# GPS_LORA_IMU.net
KiCad netlist of a schematic drawn in Altium Designer
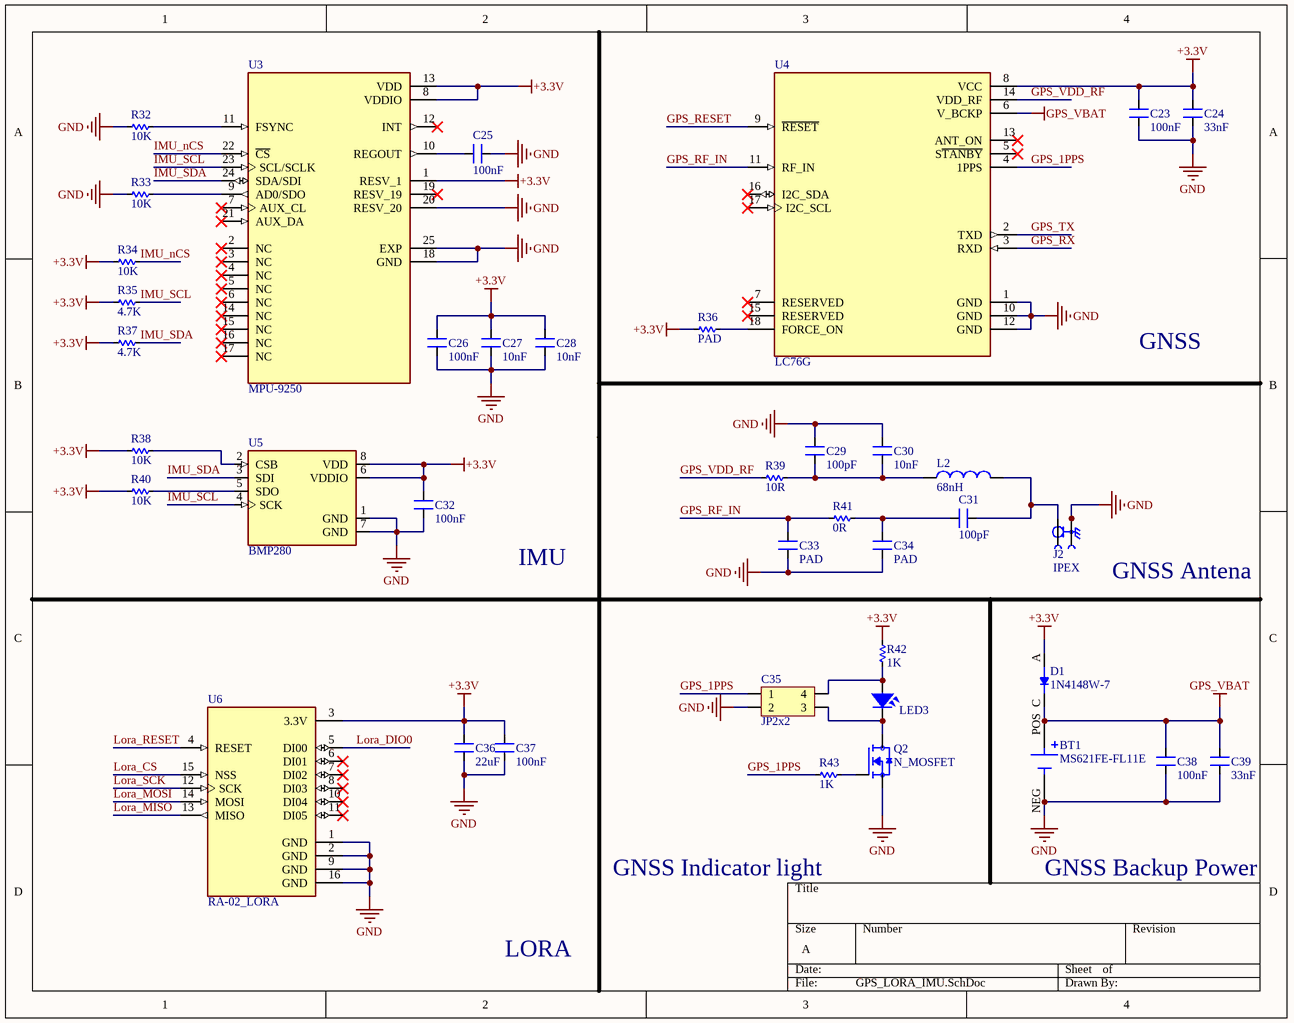
[diagram p0: GPS_LORA_IMU.SchDoc]

(export (version "E")
  (design (tool "Eeschema 10.0.6"))
  (components
    (comp (ref "BT1")
      (value "MS621FE-FL11E")
      (footprint "BAT_MS621FE-FL11E")
      (description "Coin, 6.8mm 3 V Lithium Battery Rechargeable (Secondary) 5.5mAh")
      (fields (field (name "MF") "Seiko Instruments"))
      (libsource (lib "DATN_LIB") (part "MS621FE-FL11E"))
    )
    (comp (ref "C23") (value "100nF") (footprint "CN-SMD-0603") (libsource (lib "DATN_LIB") (part "Cap-SMD")))
    (comp (ref "C24") (value "33nF") (footprint "CN-SMD-0603") (libsource (lib "DATN_LIB") (part "Cap-SMD")))
    (comp (ref "C25") (value "100nF") (footprint "CN-SMD-0603") (libsource (lib "DATN_LIB") (part "Cap-SMD")))
    (comp (ref "C26") (value "100nF") (footprint "CN-SMD-0603") (libsource (lib "DATN_LIB") (part "Cap-SMD")))
    (comp (ref "C27") (value "10nF") (footprint "CN-SMD-0603") (libsource (lib "DATN_LIB") (part "Cap-SMD")))
    (comp (ref "C28") (value "10nF") (footprint "CN-SMD-0603") (libsource (lib "DATN_LIB") (part "Cap-SMD")))
    (comp (ref "C29") (value "100pF") (footprint "CN-SMD-0603") (libsource (lib "DATN_LIB") (part "Cap-SMD")))
    (comp (ref "C30") (value "10nF") (footprint "CN-SMD-0603") (libsource (lib "DATN_LIB") (part "Cap-SMD")))
    (comp (ref "C31") (value "100pF") (footprint "CN-SMD-0603") (libsource (lib "DATN_LIB") (part "Cap-SMD")))
    (comp (ref "C32") (value "100nF") (footprint "CN-SMD-0603") (libsource (lib "DATN_LIB") (part "Cap-SMD")))
    (comp (ref "C33")
      (value "PAD")
      (footprint "PAD-CAP-SMD-0603")
      (libsource (lib "DATN_LIB") (part "Cap-SMD"))
    )
    (comp (ref "C34")
      (value "PAD")
      (footprint "PAD-CAP-SMD-0603")
      (libsource (lib "DATN_LIB") (part "Cap-SMD"))
    )
    (comp (ref "C35")
      (value "JP2x2")
      (footprint "JP2-D2T")
      (description "WR-PHD 2.54 mm Dual Socket Header")
      (fields
        (field (name "MANUFACTURER") "Würth Elektronik eiSos GmbH")
        (field (name "PARTNO") "61300421821")
        (field (name "CREATED BY") "Karrer Zheng")
      )
      (libsource (lib "DATN_LIB") (part "JP2x2"))
    )
    (comp (ref "C36") (value "22uF") (footprint "CN-SMD-1206") (libsource (lib "DATN_LIB") (part "Cap-SMD")))
    (comp (ref "C37") (value "100nF") (footprint "CN-SMD-0603") (libsource (lib "DATN_LIB") (part "Cap-SMD")))
    (comp (ref "C38") (value "100nF") (footprint "CN-SMD-0603") (libsource (lib "DATN_LIB") (part "Cap-SMD")))
    (comp (ref "C39") (value "33nF") (footprint "CN-SMD-0603") (libsource (lib "DATN_LIB") (part "Cap-SMD")))
    (comp (ref "D1")
      (value "1N4148W-7")
      (footprint "SOD3715X135N")
      (description "Diode Standard 100 V 300mA (DC) Surface Mount SOD-123")
      (fields (field (name "MF") "Diodes Inc."))
      (libsource (lib "DATN_LIB") (part "1N4148W-7"))
    )
    (comp (ref "J2")
      (value "IPEX")
      (footprint "IPEX_20279-001E-03")
      (fields (field (name "MF") "I-PEX") (field (name "MP") "20279-001E-03"))
      (libsource (lib "DATN_LIB") (part "IPEX"))
    )
    (comp (ref "L2")
      (value "68nH")
      (footprint "SMD_Inductor_0603")
      (description "INDUCTOR wire-wound")
      (fields (field (name "MP") "LQW2BAN68NG00L"))
      (libsource (lib "DATN_LIB") (part "SMD-Wire-Inductor"))
    )
    (comp (ref "LED3")
      (value "LED")
      (footprint "LED-0805-Green")
      (libsource (lib "DATN_LIB") (part "LED SMD"))
    )
    (comp (ref "Q2")
      (value "N_MOSFET")
      (footprint "SOT-23-3")
      (fields (field (name "MF") "Vishay Siliconix") (field (name "MP") "SI2306BDS-T1-GE3"))
      (libsource (lib "DATN_LIB") (part "N_MOSFET"))
    )
    (comp (ref "R32")
      (value "10K")
      (footprint "RES-SMD-0603")
      (fields
        (field (name "MANUFACTURER") "Generic Components")
        (field (name "PUBLISHER") "Altium Hobart Technology Centre")
      )
      (libsource (lib "DATN_LIB") (part "Res-SMD"))
    )
    (comp (ref "R33")
      (value "10K")
      (footprint "RES-SMD-0603")
      (fields
        (field (name "MANUFACTURER") "Generic Components")
        (field (name "PUBLISHER") "Altium Hobart Technology Centre")
      )
      (libsource (lib "DATN_LIB") (part "Res-SMD"))
    )
    (comp (ref "R34")
      (value "10K")
      (footprint "RES-SMD-0603")
      (fields
        (field (name "MANUFACTURER") "Generic Components")
        (field (name "PUBLISHER") "Altium Hobart Technology Centre")
      )
      (libsource (lib "DATN_LIB") (part "Res-SMD"))
    )
    (comp (ref "R35")
      (value "4.7K")
      (footprint "RES-SMD-0603")
      (fields
        (field (name "MANUFACTURER") "Generic Components")
        (field (name "PUBLISHER") "Altium Hobart Technology Centre")
      )
      (libsource (lib "DATN_LIB") (part "Res-SMD"))
    )
    (comp (ref "R36")
      (value "PAD")
      (footprint "PAD-RES-SMD-0603")
      (description "Resistor")
      (fields
        (field (name "MANUFACTURER") "Generic Components")
        (field (name "PUBLISHER") "Altium Hobart Technology Centre")
      )
      (libsource (lib "DATN_LIB") (part "Res-SMD"))
    )
    (comp (ref "R37")
      (value "4.7K")
      (footprint "RES-SMD-0603")
      (fields
        (field (name "MANUFACTURER") "Generic Components")
        (field (name "PUBLISHER") "Altium Hobart Technology Centre")
      )
      (libsource (lib "DATN_LIB") (part "Res-SMD"))
    )
    (comp (ref "R38")
      (value "10K")
      (footprint "RES-SMD-0603")
      (fields
        (field (name "MANUFACTURER") "Generic Components")
        (field (name "PUBLISHER") "Altium Hobart Technology Centre")
      )
      (libsource (lib "DATN_LIB") (part "Res-SMD"))
    )
    (comp (ref "R39")
      (value "10R")
      (footprint "RES-SMD-0603")
      (description "Resistor")
      (fields
        (field (name "MANUFACTURER") "Generic Components")
        (field (name "PUBLISHER") "Altium Hobart Technology Centre")
      )
      (libsource (lib "DATN_LIB") (part "Res-SMD"))
    )
    (comp (ref "R40")
      (value "10K")
      (footprint "RES-SMD-0603")
      (fields
        (field (name "MANUFACTURER") "Generic Components")
        (field (name "PUBLISHER") "Altium Hobart Technology Centre")
      )
      (libsource (lib "DATN_LIB") (part "Res-SMD"))
    )
    (comp (ref "R41")
      (value "0R")
      (footprint "RES-SMD-0603")
      (description "Resistor")
      (fields
        (field (name "MANUFACTURER") "Generic Components")
        (field (name "PUBLISHER") "Altium Hobart Technology Centre")
      )
      (libsource (lib "DATN_LIB") (part "Res-SMD"))
    )
    (comp (ref "R42")
      (value "1K")
      (footprint "RES-SMD-0603")
      (description "Resistor")
      (fields
        (field (name "MANUFACTURER") "Generic Components")
        (field (name "PUBLISHER") "Altium Hobart Technology Centre")
      )
      (libsource (lib "DATN_LIB") (part "Res-SMD"))
    )
    (comp (ref "R43")
      (value "1K")
      (footprint "RES-SMD-0603")
      (description "Resistor")
      (fields
        (field (name "MANUFACTURER") "Generic Components")
        (field (name "PUBLISHER") "Altium Hobart Technology Centre")
      )
      (libsource (lib "DATN_LIB") (part "Res-SMD"))
    )
    (comp (ref "U3")
      (value "MPU-9250")
      (footprint "QFN40P300X300X105-25N")
      (fields (field (name "MF") "TDK InvenSense"))
      (libsource (lib "DATN_LIB") (part "MPU-9250"))
    )
    (comp (ref "U4")
      (value "LC76G")
      (footprint "XCVR_LC76G")
      (fields (field (name "MF") "Quectel"))
      (libsource (lib "DATN_LIB") (part "LC76G"))
    )
    (comp (ref "U5")
      (value "BMP280")
      (footprint "XDCR_BMP280")
      (description "BMP280 Absolute Barometric Pressure Sensor for Battery Powered Devices 2 x 2.5mm")
      (libsource (lib "DATN_LIB") (part "BMP280"))
    )
    (comp (ref "U6")
      (value "RA-02_LORA")
      (footprint "MODULE_RA-02_LORA")
      (description "Ra-02 LoRa RF M5Stack Platform Evaluation Expansion Board")
      (libsource (lib "DATN_LIB") (part "RA-02_LORA"))
    )
  )
  (nets
    (net (code "1") (name "+3.3V") (class "Default")
      (node (ref "C23") (pin "2") (pinfunction "2_2") (pintype "passive"))
      (node (ref "C24") (pin "2") (pinfunction "2_2") (pintype "passive"))
      (node (ref "C26") (pin "2") (pinfunction "2_2") (pintype "passive"))
      (node (ref "C27") (pin "2") (pinfunction "2_2") (pintype "passive"))
      (node (ref "C28") (pin "2") (pinfunction "2_2") (pintype "passive"))
      (node (ref "C32") (pin "2") (pinfunction "2_2") (pintype "passive"))
      (node (ref "C36") (pin "2") (pinfunction "2_2") (pintype "passive"))
      (node (ref "C37") (pin "2") (pinfunction "2_2") (pintype "passive"))
      (node (ref "D1") (pin "A") (pinfunction "A_A") (pintype "passive"))
      (node (ref "R34") (pin "1") (pinfunction "1_1") (pintype "passive"))
      (node (ref "R35") (pin "1") (pinfunction "1_1") (pintype "passive"))
      (node (ref "R36") (pin "2") (pinfunction "2_2") (pintype "passive"))
      (node (ref "R37") (pin "1") (pinfunction "1_1") (pintype "passive"))
      (node (ref "R38") (pin "2") (pinfunction "2_2") (pintype "passive"))
      (node (ref "R40") (pin "2") (pinfunction "2_2") (pintype "passive"))
      (node (ref "R42") (pin "2") (pinfunction "2_2") (pintype "passive"))
      (node (ref "U3") (pin "1") (pinfunction "RESV_1_1") (pintype "power_in"))
      (node (ref "U3") (pin "13") (pinfunction "VDD_13") (pintype "power_in"))
      (node (ref "U3") (pin "8") (pinfunction "VDDIO_8") (pintype "power_in"))
      (node (ref "U4") (pin "8") (pinfunction "VCC_8") (pintype "power_in"))
      (node (ref "U5") (pin "6") (pinfunction "VDDIO_6") (pintype "power_in"))
      (node (ref "U5") (pin "8") (pinfunction "VDD_8") (pintype "power_in"))
      (node (ref "U6") (pin "3") (pinfunction "3.3V_3") (pintype "power_in"))
    )
    (net (code "2") (name "/GPS_1PPS") (class "Default")
      (node (ref "C35") (pin "1") (pinfunction "1_1") (pintype "passive"))
      (node (ref "R43") (pin "1") (pinfunction "1_1") (pintype "passive"))
      (node (ref "U4") (pin "4") (pinfunction "1PPS_4") (pintype "passive"))
    )
    (net (code "3") (name "/GPS_RESET") (class "Default")
      (node (ref "U4") (pin "9") (pinfunction "~{RESET}_9") (pintype "input"))
    )
    (net (code "4") (name "/GPS_RF_IN") (class "Default")
      (node (ref "C33") (pin "1") (pinfunction "1_1") (pintype "passive"))
      (node (ref "R41") (pin "2") (pinfunction "2_2") (pintype "passive"))
      (node (ref "U4") (pin "11") (pinfunction "RF_IN_11") (pintype "input"))
    )
    (net (code "5") (name "/GPS_RX") (class "Default")
      (node (ref "U4") (pin "3") (pinfunction "RXD_3") (pintype "input"))
    )
    (net (code "6") (name "/GPS_TX") (class "Default")
      (node (ref "U4") (pin "2") (pinfunction "TXD_2") (pintype "output"))
    )
    (net (code "7") (name "/GPS_VDD_RF") (class "Default")
      (node (ref "R39") (pin "2") (pinfunction "2_2") (pintype "passive"))
      (node (ref "U4") (pin "14") (pinfunction "VDD_RF_14") (pintype "power_in"))
    )
    (net (code "8") (name "/IMU_SCL") (class "Default")
      (node (ref "R35") (pin "2") (pinfunction "2_2") (pintype "passive"))
      (node (ref "U3") (pin "23") (pinfunction "SCL/SCLK_23") (pintype "input"))
      (node (ref "U5") (pin "4") (pinfunction "SCK_4") (pintype "input"))
    )
    (net (code "9") (name "/IMU_SDA") (class "Default")
      (node (ref "R37") (pin "2") (pinfunction "2_2") (pintype "passive"))
      (node (ref "U3") (pin "24") (pinfunction "SDA/SDI_24") (pintype "bidirectional"))
      (node (ref "U5") (pin "3") (pinfunction "SDI_3") (pintype "bidirectional"))
    )
    (net (code "10") (name "/IMU_nCS") (class "Default")
      (node (ref "R34") (pin "2") (pinfunction "2_2") (pintype "passive"))
      (node (ref "U3") (pin "22") (pinfunction "~{CS}_22") (pintype "input"))
    )
    (net (code "11") (name "/Lora_CS") (class "Default")
      (node (ref "U6") (pin "15") (pinfunction "NSS_15") (pintype "input"))
    )
    (net (code "12") (name "/Lora_DIO0") (class "Default")
      (node (ref "U6") (pin "5") (pinfunction "DI00_5") (pintype "bidirectional"))
    )
    (net (code "13") (name "/Lora_MISO") (class "Default")
      (node (ref "U6") (pin "13") (pinfunction "MISO_13") (pintype "output"))
    )
    (net (code "14") (name "/Lora_MOSI") (class "Default")
      (node (ref "U6") (pin "14") (pinfunction "MOSI_14") (pintype "input"))
    )
    (net (code "15") (name "/Lora_RESET") (class "Default")
      (node (ref "U6") (pin "4") (pinfunction "RESET_4") (pintype "input"))
    )
    (net (code "16") (name "/Lora_SCK") (class "Default")
      (node (ref "U6") (pin "12") (pinfunction "SCK_12") (pintype "input"))
    )
    (net (code "17") (name "GND") (class "Default")
      (node (ref "BT1") (pin "NEG") (pinfunction "NEG_NEG") (pintype "passive"))
      (node (ref "C23") (pin "1") (pinfunction "1_1") (pintype "passive"))
      (node (ref "C24") (pin "1") (pinfunction "1_1") (pintype "passive"))
      (node (ref "C25") (pin "2") (pinfunction "2_2") (pintype "passive"))
      (node (ref "C26") (pin "1") (pinfunction "1_1") (pintype "passive"))
      (node (ref "C27") (pin "1") (pinfunction "1_1") (pintype "passive"))
      (node (ref "C28") (pin "1") (pinfunction "1_1") (pintype "passive"))
      (node (ref "C29") (pin "2") (pinfunction "2_2") (pintype "passive"))
      (node (ref "C30") (pin "2") (pinfunction "2_2") (pintype "passive"))
      (node (ref "C32") (pin "1") (pinfunction "1_1") (pintype "passive"))
      (node (ref "C33") (pin "2") (pinfunction "2_2") (pintype "passive"))
      (node (ref "C34") (pin "2") (pinfunction "2_2") (pintype "passive"))
      (node (ref "C35") (pin "2") (pinfunction "2_2") (pintype "passive"))
      (node (ref "C36") (pin "1") (pinfunction "1_1") (pintype "passive"))
      (node (ref "C37") (pin "1") (pinfunction "1_1") (pintype "passive"))
      (node (ref "C38") (pin "1") (pinfunction "1_1") (pintype "passive"))
      (node (ref "C39") (pin "1") (pinfunction "1_1") (pintype "passive"))
      (node (ref "J2") (pin "2") (pinfunction "GROUND_2") (pintype "passive"))
      (node (ref "J2") (pin "3") (pinfunction "GROUND_3") (pintype "passive"))
      (node (ref "Q2") (pin "2") (pinfunction "S_2") (pintype "passive"))
      (node (ref "R32") (pin "2") (pinfunction "2_2") (pintype "passive"))
      (node (ref "R33") (pin "2") (pinfunction "2_2") (pintype "passive"))
      (node (ref "U3") (pin "18") (pinfunction "GND_18") (pintype "power_in"))
      (node (ref "U3") (pin "20") (pinfunction "RESV_20_20") (pintype "power_in"))
      (node (ref "U3") (pin "25") (pinfunction "EXP_25") (pintype "passive"))
      (node (ref "U4") (pin "1") (pinfunction "GND_1") (pintype "power_in"))
      (node (ref "U4") (pin "10") (pinfunction "GND_10") (pintype "power_in"))
      (node (ref "U4") (pin "12") (pinfunction "GND_12") (pintype "power_in"))
      (node (ref "U5") (pin "1") (pinfunction "GND_1") (pintype "power_in"))
      (node (ref "U5") (pin "7") (pinfunction "GND_7") (pintype "power_in"))
      (node (ref "U6") (pin "1") (pinfunction "GND_1") (pintype "power_in"))
      (node (ref "U6") (pin "16") (pinfunction "GND_16") (pintype "power_in"))
      (node (ref "U6") (pin "2") (pinfunction "GND_2") (pintype "power_in"))
      (node (ref "U6") (pin "9") (pinfunction "GND_9") (pintype "power_in"))
    )
    (net (code "18") (name "GPS_VBAT") (class "Default")
      (node (ref "BT1") (pin "POS") (pinfunction "POS_POS") (pintype "passive"))
      (node (ref "C38") (pin "2") (pinfunction "2_2") (pintype "passive"))
      (node (ref "C39") (pin "2") (pinfunction "2_2") (pintype "passive"))
      (node (ref "D1") (pin "C") (pinfunction "K_C") (pintype "passive"))
      (node (ref "U4") (pin "6") (pinfunction "V_BCKP_6") (pintype "power_in"))
    )
    (net (code "19") (name "Net-(C29-Pad1)") (class "Default")
      (node (ref "C29") (pin "1") (pinfunction "1_1") (pintype "passive"))
      (node (ref "C30") (pin "1") (pinfunction "1_1") (pintype "passive"))
      (node (ref "L2") (pin "1") (pinfunction "1_1") (pintype "passive"))
      (node (ref "R39") (pin "1") (pinfunction "1_1") (pintype "passive"))
    )
    (net (code "20") (name "Net-(C31-Pad2)") (class "Default")
      (node (ref "C31") (pin "2") (pinfunction "2_2") (pintype "passive"))
      (node (ref "C34") (pin "1") (pinfunction "1_1") (pintype "passive"))
      (node (ref "R41") (pin "1") (pinfunction "1_1") (pintype "passive"))
    )
    (net (code "21") (name "Net-(C35-Pad4)") (class "Default")
      (node (ref "C35") (pin "4") (pinfunction "4_4") (pintype "passive"))
      (node (ref "LED3") (pin "1") (pinfunction "1_1") (pintype "passive"))
      (node (ref "R42") (pin "1") (pinfunction "1_1") (pintype "passive"))
    )
    (net (code "22") (name "Net-(J2-SIGNAL)") (class "Default")
      (node (ref "C31") (pin "1") (pinfunction "1_1") (pintype "passive"))
      (node (ref "J2") (pin "1") (pinfunction "SIGNAL_1") (pintype "passive"))
      (node (ref "L2") (pin "2") (pinfunction "2_2") (pintype "passive"))
    )
    (net (code "23") (name "Net-(Q2-D)") (class "Default")
      (node (ref "C35") (pin "3") (pinfunction "3_3") (pintype "passive"))
      (node (ref "LED3") (pin "2") (pinfunction "2_2") (pintype "passive"))
      (node (ref "Q2") (pin "3") (pinfunction "D_3") (pintype "passive"))
    )
    (net (code "24") (name "Net-(Q2-G)") (class "Default")
      (node (ref "Q2") (pin "1") (pinfunction "G_1") (pintype "passive"))
      (node (ref "R43") (pin "2") (pinfunction "2_2") (pintype "passive"))
    )
    (net (code "25") (name "Net-(U3-AD0{slash}SDO)") (class "Default")
      (node (ref "R33") (pin "1") (pinfunction "1_1") (pintype "passive"))
      (node (ref "U3") (pin "9") (pinfunction "AD0/SDO_9") (pintype "output"))
    )
    (net (code "26") (name "Net-(U3-FSYNC)") (class "Default")
      (node (ref "R32") (pin "1") (pinfunction "1_1") (pintype "passive"))
      (node (ref "U3") (pin "11") (pinfunction "FSYNC_11") (pintype "input"))
    )
    (net (code "27") (name "Net-(U3-REGOUT)") (class "Default")
      (node (ref "C25") (pin "1") (pinfunction "1_1") (pintype "passive"))
      (node (ref "U3") (pin "10") (pinfunction "REGOUT_10") (pintype "output"))
    )
    (net (code "28") (name "Net-(U4-FORCE_ON)") (class "Default")
      (node (ref "R36") (pin "1") (pinfunction "1_1") (pintype "passive"))
      (node (ref "U4") (pin "18") (pinfunction "FORCE_ON_18") (pintype "passive"))
    )
    (net (code "29") (name "Net-(U5-CSB)") (class "Default")
      (node (ref "R38") (pin "1") (pinfunction "1_1") (pintype "passive"))
      (node (ref "U5") (pin "2") (pinfunction "CSB_2") (pintype "input"))
    )
    (net (code "30") (name "Net-(U5-SDO)") (class "Default")
      (node (ref "R40") (pin "1") (pinfunction "1_1") (pintype "passive"))
      (node (ref "U5") (pin "5") (pinfunction "SDO_5") (pintype "bidirectional"))
    )
    (net (code "31") (name "unconnected-(U3-AUX_CL-Pad7)") (class "Default")
      (node (ref "U3") (pin "7") (pinfunction "AUX_CL_7") (pintype "input+no_connect"))
    )
    (net (code "32") (name "unconnected-(U3-AUX_DA-Pad21)") (class "Default")
      (node (ref "U3") (pin "21") (pinfunction "AUX_DA_21") (pintype "input+no_connect"))
    )
    (net (code "33") (name "unconnected-(U3-INT-Pad12)") (class "Default")
      (node (ref "U3") (pin "12") (pinfunction "INT_12") (pintype "output+no_connect"))
    )
    (net (code "34") (name "unconnected-(U3-NC-Pad2)") (class "Default")
      (node (ref "U3") (pin "2") (pinfunction "NC_2") (pintype "passive+no_connect"))
    )
    (net (code "35") (name "unconnected-(U3-NC-Pad3)") (class "Default")
      (node (ref "U3") (pin "3") (pinfunction "NC_3") (pintype "passive+no_connect"))
    )
    (net (code "36") (name "unconnected-(U3-NC-Pad4)") (class "Default")
      (node (ref "U3") (pin "4") (pinfunction "NC_4") (pintype "passive+no_connect"))
    )
    (net (code "37") (name "unconnected-(U3-NC-Pad5)") (class "Default")
      (node (ref "U3") (pin "5") (pinfunction "NC_5") (pintype "passive+no_connect"))
    )
    (net (code "38") (name "unconnected-(U3-NC-Pad6)") (class "Default")
      (node (ref "U3") (pin "6") (pinfunction "NC_6") (pintype "passive+no_connect"))
    )
    (net (code "39") (name "unconnected-(U3-NC-Pad14)") (class "Default")
      (node (ref "U3") (pin "14") (pinfunction "NC_14") (pintype "passive+no_connect"))
    )
    (net (code "40") (name "unconnected-(U3-NC-Pad15)") (class "Default")
      (node (ref "U3") (pin "15") (pinfunction "NC_15") (pintype "passive+no_connect"))
    )
    (net (code "41") (name "unconnected-(U3-NC-Pad16)") (class "Default")
      (node (ref "U3") (pin "16") (pinfunction "NC_16") (pintype "passive+no_connect"))
    )
    (net (code "42") (name "unconnected-(U3-NC-Pad17)") (class "Default")
      (node (ref "U3") (pin "17") (pinfunction "NC_17") (pintype "passive+no_connect"))
    )
    (net (code "43") (name "unconnected-(U3-RESV_19-Pad19)") (class "Default")
      (node (ref "U3") (pin "19") (pinfunction "RESV_19_19") (pintype "passive+no_connect"))
    )
    (net (code "44") (name "unconnected-(U4-ANT_ON-Pad13)") (class "Default")
      (node (ref "U4") (pin "13") (pinfunction "ANT_ON_13") (pintype "passive+no_connect"))
    )
    (net (code "45") (name "unconnected-(U4-I2C_SCL-Pad17)") (class "Default")
      (node (ref "U4") (pin "17") (pinfunction "I2C_SCL_17") (pintype "input+no_connect"))
    )
    (net (code "46") (name "unconnected-(U4-I2C_SDA-Pad16)") (class "Default")
      (node (ref "U4") (pin "16") (pinfunction "I2C_SDA_16") (pintype "bidirectional+no_connect"))
    )
    (net (code "47") (name "unconnected-(U4-RESERVED-Pad7)") (class "Default")
      (node (ref "U4") (pin "7") (pinfunction "RESERVED_7") (pintype "passive+no_connect"))
    )
    (net (code "48") (name "unconnected-(U4-RESERVED-Pad15)") (class "Default")
      (node (ref "U4") (pin "15") (pinfunction "RESERVED_15") (pintype "passive+no_connect"))
    )
    (net (code "49") (name "unconnected-(U4-S~{TANBY}-Pad5)") (class "Default")
      (node (ref "U4") (pin "5") (pinfunction "S~{TANBY}_5") (pintype "passive+no_connect"))
    )
    (net (code "50") (name "unconnected-(U6-DI01-Pad6)") (class "Default")
      (node (ref "U6") (pin "6") (pinfunction "DI01_6") (pintype "bidirectional+no_connect"))
    )
    (net (code "51") (name "unconnected-(U6-DI02-Pad7)") (class "Default")
      (node (ref "U6") (pin "7") (pinfunction "DI02_7") (pintype "bidirectional+no_connect"))
    )
    (net (code "52") (name "unconnected-(U6-DI03-Pad8)") (class "Default")
      (node (ref "U6") (pin "8") (pinfunction "DI03_8") (pintype "bidirectional+no_connect"))
    )
    (net (code "53") (name "unconnected-(U6-DI04-Pad10)") (class "Default")
      (node (ref "U6") (pin "10") (pinfunction "DI04_10") (pintype "bidirectional+no_connect"))
    )
    (net (code "54") (name "unconnected-(U6-DI05-Pad11)") (class "Default")
      (node (ref "U6") (pin "11") (pinfunction "DI05_11") (pintype "bidirectional+no_connect"))
    )
  )
)
